# lmx2572_single_ended.net
KiCad netlist of a schematic drawn in EAGLE
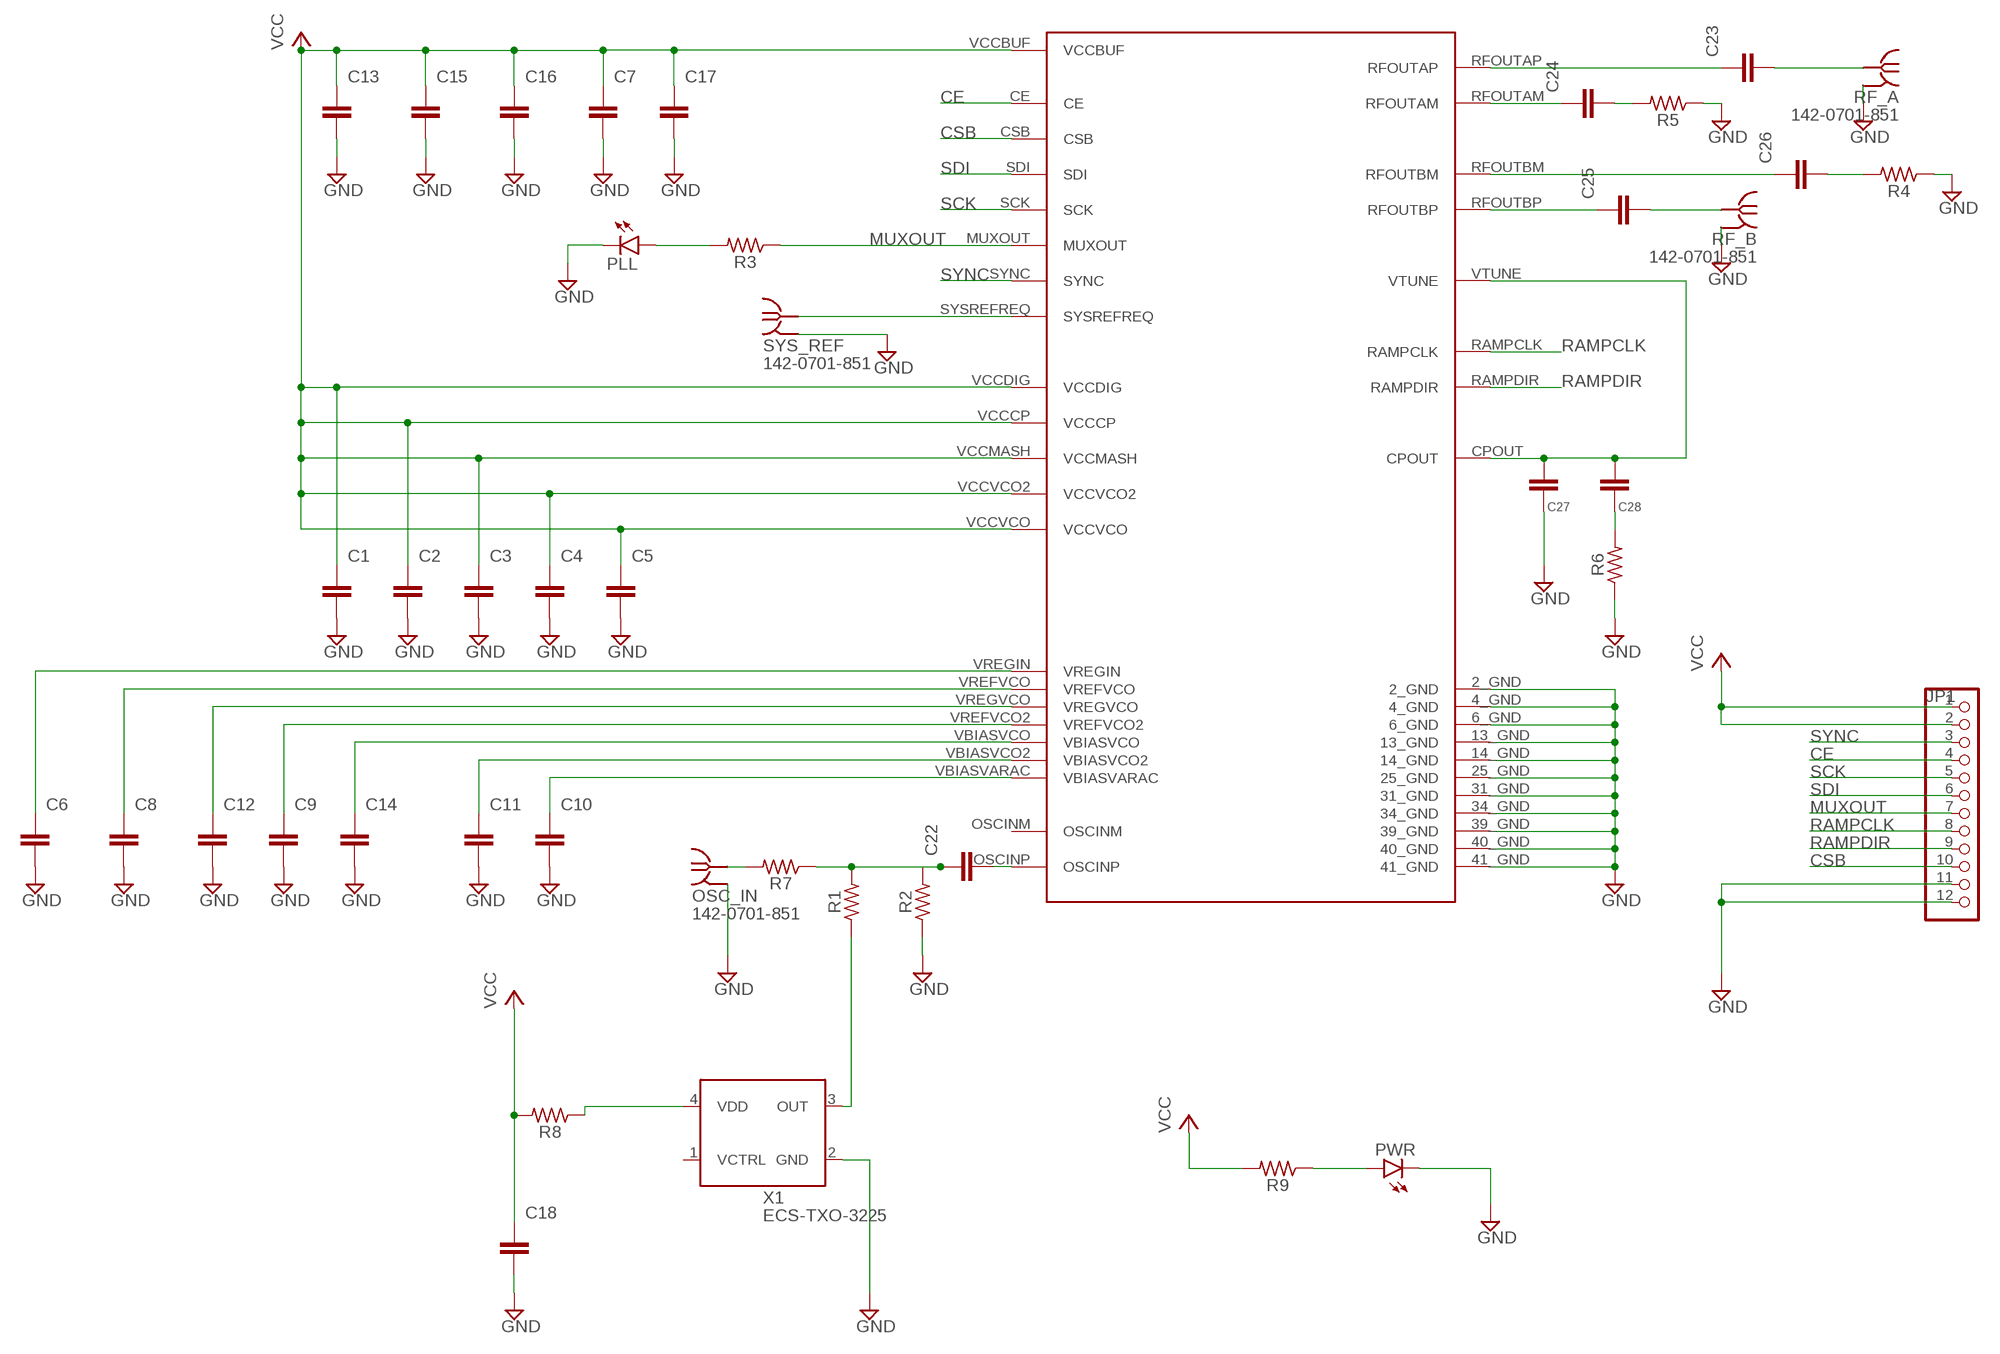
[diagram p0: schematic, sheet 1]

(export (version "E")
  (design (tool "Eeschema 10.0.6"))
  (components
    (comp (ref "C1")
      (value "1.0uF")
      (footprint "eagle-import:.0603-B-NOSILK")
      (libsource (lib "eagle-import") (part "C-EU0603-B-NOSILK"))
    )
    (comp (ref "C2")
      (value "1.0uF")
      (footprint "eagle-import:.0603-B-NOSILK")
      (libsource (lib "eagle-import") (part "C-EU0603-B-NOSILK"))
    )
    (comp (ref "C3")
      (value "1.0uF")
      (footprint "eagle-import:.0603-B-NOSILK")
      (libsource (lib "eagle-import") (part "C-EU0603-B-NOSILK"))
    )
    (comp (ref "C4")
      (value "1.0uF")
      (footprint "eagle-import:.0603-B-NOSILK")
      (libsource (lib "eagle-import") (part "C-EU0603-B-NOSILK"))
    )
    (comp (ref "C5")
      (value "1.0uF")
      (footprint "eagle-import:.0603-B-NOSILK")
      (libsource (lib "eagle-import") (part "C-EU0603-B-NOSILK"))
    )
    (comp (ref "C6")
      (value "1.0uF")
      (footprint "eagle-import:.0603-B-NOSILK")
      (libsource (lib "eagle-import") (part "C-EU0603-B-NOSILK"))
    )
    (comp (ref "C7")
      (value "0.1uF")
      (footprint "eagle-import:.0603-B-NOSILK")
      (libsource (lib "eagle-import") (part "C-EU0603-B-NOSILK"))
    )
    (comp (ref "C8")
      (value "10uF")
      (footprint "eagle-import:.0603-B-NOSILK")
      (libsource (lib "eagle-import") (part "C-EU0603-B-NOSILK"))
    )
    (comp (ref "C9")
      (value "10uF")
      (footprint "eagle-import:.0603-B-NOSILK")
      (libsource (lib "eagle-import") (part "C-EU0603-B-NOSILK"))
    )
    (comp (ref "C10")
      (value "10uF")
      (footprint "eagle-import:.0603-B-NOSILK")
      (libsource (lib "eagle-import") (part "C-EU0603-B-NOSILK"))
    )
    (comp (ref "C11")
      (value "0.1uF")
      (footprint "eagle-import:.0603-B-NOSILK")
      (libsource (lib "eagle-import") (part "C-EU0603-B-NOSILK"))
    )
    (comp (ref "C12")
      (value "10nF")
      (footprint "eagle-import:.0603-B-NOSILK")
      (libsource (lib "eagle-import") (part "C-EU0603-B-NOSILK"))
    )
    (comp (ref "C13")
      (value "0.1uF")
      (footprint "eagle-import:.0603-B-NOSILK")
      (libsource (lib "eagle-import") (part "C-EU0603-B-NOSILK"))
    )
    (comp (ref "C14")
      (value "470pF")
      (footprint "eagle-import:.0603-B-NOSILK")
      (libsource (lib "eagle-import") (part "C-EU0603-B-NOSILK"))
    )
    (comp (ref "C15")
      (value "10uF")
      (footprint "eagle-import:.0603-B-NOSILK")
      (libsource (lib "eagle-import") (part "C-EU0603-B-NOSILK"))
    )
    (comp (ref "C16")
      (value "10uF")
      (footprint "eagle-import:.0603-B-NOSILK")
      (libsource (lib "eagle-import") (part "C-EU0603-B-NOSILK"))
    )
    (comp (ref "C17")
      (value "0.1uF")
      (footprint "eagle-import:.0603-B-NOSILK")
      (libsource (lib "eagle-import") (part "C-EU0603-B-NOSILK"))
    )
    (comp (ref "C18")
      (value "10uF")
      (footprint "eagle-import:.0603-B-NOSILK")
      (libsource (lib "eagle-import") (part "C-EU0603-B-NOSILK"))
    )
    (comp (ref "C22")
      (value "0.1uF")
      (footprint "eagle-import:.0402-C-NOSILK")
      (libsource (lib "eagle-import") (part "C-EU0402-C-NOSILK"))
    )
    (comp (ref "C23")
      (value "100PF")
      (footprint "eagle-import:.0402-C-NOSILK")
      (libsource (lib "eagle-import") (part "C-EU0402-C-NOSILK"))
    )
    (comp (ref "C24")
      (value "100PF")
      (footprint "eagle-import:.0402-C-NOSILK")
      (libsource (lib "eagle-import") (part "C-EU0402-C-NOSILK"))
    )
    (comp (ref "C25")
      (value "100PF")
      (footprint "eagle-import:.0402-C-NOSILK")
      (libsource (lib "eagle-import") (part "C-EU0402-C-NOSILK"))
    )
    (comp (ref "C26")
      (value "100PF")
      (footprint "eagle-import:.0402-C-NOSILK")
      (libsource (lib "eagle-import") (part "C-EU0402-C-NOSILK"))
    )
    (comp (ref "C27")
      (value "4.7nf")
      (footprint "eagle-import:.0402-C-NOSILK")
      (libsource (lib "eagle-import") (part "C-EU0402-C-NOSILK"))
    )
    (comp (ref "C28")
      (value "220nf")
      (footprint "eagle-import:.0402-C-NOSILK")
      (libsource (lib "eagle-import") (part "C-EU0402-C-NOSILK"))
    )
    (comp (ref "JP1")
      (value "PINHD-1X12")
      (footprint "eagle-import:1X12")
      (libsource (lib "eagle-import") (part "PINHD-1X12"))
    )
    (comp (ref "OSC_IN")
      (value "142-0701-851")
      (footprint "eagle-import:142-0701-851")
      (libsource (lib "eagle-import") (part "142-0701-851"))
    )
    (comp (ref "PLL")
      (value "LEDCHIP-LED0603")
      (footprint "eagle-import:CHIP-LED0603")
      (libsource (lib "eagle-import") (part "LEDCHIP-LED0603"))
    )
    (comp (ref "PWR")
      (value "LEDCHIP-LED0603")
      (footprint "eagle-import:CHIP-LED0603")
      (libsource (lib "eagle-import") (part "LEDCHIP-LED0603"))
    )
    (comp (ref "R1")
      (value "0")
      (footprint "eagle-import:.0402-C-NOSILK")
      (libsource (lib "eagle-import") (part "R-US_0402-C-NOSILK"))
    )
    (comp (ref "R2")
      (value "50")
      (footprint "eagle-import:.0402-C-NOSILK")
      (libsource (lib "eagle-import") (part "R-US_0402-C-NOSILK"))
    )
    (comp (ref "R3")
      (value "330")
      (footprint "eagle-import:.0603-B-NOSILK")
      (libsource (lib "eagle-import") (part "R-US_0603-B-NOSILK"))
    )
    (comp (ref "R4")
      (value "50")
      (footprint "eagle-import:.0402-C-NOSILK")
      (libsource (lib "eagle-import") (part "R-US_0402-C-NOSILK"))
    )
    (comp (ref "R5")
      (value "50")
      (footprint "eagle-import:.0402-C-NOSILK")
      (libsource (lib "eagle-import") (part "R-US_0402-C-NOSILK"))
    )
    (comp (ref "R6")
      (value "100")
      (footprint "eagle-import:.0402-C-NOSILK")
      (libsource (lib "eagle-import") (part "R-US_0402-C-NOSILK"))
    )
    (comp (ref "R7")
      (value "0")
      (footprint "eagle-import:.0402-C-NOSILK")
      (libsource (lib "eagle-import") (part "R-US_0402-C-NOSILK"))
    )
    (comp (ref "R8")
      (value "0")
      (footprint "eagle-import:.0402-C-NOSILK")
      (libsource (lib "eagle-import") (part "R-US_0402-C-NOSILK"))
    )
    (comp (ref "R9")
      (value "330")
      (footprint "eagle-import:.0603-B-NOSILK")
      (libsource (lib "eagle-import") (part "R-US_0603-B-NOSILK"))
    )
    (comp (ref "RF_A")
      (value "142-0701-851")
      (footprint "eagle-import:142-0701-851")
      (libsource (lib "eagle-import") (part "142-0701-851"))
    )
    (comp (ref "RF_B")
      (value "142-0701-851")
      (footprint "eagle-import:142-0701-851")
      (libsource (lib "eagle-import") (part "142-0701-851"))
    )
    (comp (ref "SYS_REF")
      (value "142-0701-851")
      (footprint "eagle-import:142-0701-851")
      (libsource (lib "eagle-import") (part "142-0701-851"))
    )
    (comp (ref "U$1")
      (value "LMX2572_QFN")
      (footprint "eagle-import:LMX2572_QFN")
      (libsource (lib "eagle-import") (part "LMX2572_QFN"))
    )
    (comp (ref "X1")
      (value "ECS-TXO-3225")
      (footprint "eagle-import:3.2X2.5")
      (libsource (lib "eagle-import") (part "ECS-TXO-3225"))
    )
  )
  (nets
    (net (code "1") (name "/CE") (class "Default")
      (node (ref "JP1") (pin "4") (pinfunction "4_4") (pintype "passive"))
      (node (ref "U$1") (pin "CE") (pinfunction "CE_CE") (pintype "bidirectional"))
    )
    (net (code "2") (name "/CSB") (class "Default")
      (node (ref "JP1") (pin "10") (pinfunction "10_10") (pintype "passive"))
      (node (ref "U$1") (pin "CSB") (pinfunction "CSB_CSB") (pintype "bidirectional"))
    )
    (net (code "3") (name "/MUXOUT") (class "Default")
      (node (ref "JP1") (pin "7") (pinfunction "7_7") (pintype "passive"))
      (node (ref "R3") (pin "1") (pinfunction "1_1") (pintype "passive"))
      (node (ref "U$1") (pin "MUXOUT") (pinfunction "MUXOUT_MUXOUT") (pintype "bidirectional"))
    )
    (net (code "4") (name "/RAMPCLK") (class "Default")
      (node (ref "JP1") (pin "8") (pinfunction "8_8") (pintype "passive"))
      (node (ref "U$1") (pin "RAMPCLK") (pinfunction "RAMPCLK_RAMPCLK") (pintype "bidirectional"))
    )
    (net (code "5") (name "/RAMPDIR") (class "Default")
      (node (ref "JP1") (pin "9") (pinfunction "9_9") (pintype "passive"))
      (node (ref "U$1") (pin "RAMPDIR") (pinfunction "RAMPDIR_RAMPDIR") (pintype "bidirectional"))
    )
    (net (code "6") (name "/SCK") (class "Default")
      (node (ref "JP1") (pin "5") (pinfunction "5_5") (pintype "passive"))
      (node (ref "U$1") (pin "SCK") (pinfunction "SCK_SCK") (pintype "bidirectional"))
    )
    (net (code "7") (name "/SDI") (class "Default")
      (node (ref "JP1") (pin "6") (pinfunction "6_6") (pintype "passive"))
      (node (ref "U$1") (pin "SDI") (pinfunction "SDI_SDI") (pintype "bidirectional"))
    )
    (net (code "8") (name "/SYNC") (class "Default")
      (node (ref "JP1") (pin "3") (pinfunction "3_3") (pintype "passive"))
      (node (ref "U$1") (pin "SYNC") (pinfunction "SYNC_SYNC") (pintype "bidirectional"))
    )
    (net (code "9") (name "GND") (class "Default")
      (node (ref "C1") (pin "2") (pinfunction "2_2") (pintype "passive"))
      (node (ref "C10") (pin "2") (pinfunction "2_2") (pintype "passive"))
      (node (ref "C11") (pin "2") (pinfunction "2_2") (pintype "passive"))
      (node (ref "C12") (pin "2") (pinfunction "2_2") (pintype "passive"))
      (node (ref "C13") (pin "2") (pinfunction "2_2") (pintype "passive"))
      (node (ref "C14") (pin "2") (pinfunction "2_2") (pintype "passive"))
      (node (ref "C15") (pin "2") (pinfunction "2_2") (pintype "passive"))
      (node (ref "C16") (pin "2") (pinfunction "2_2") (pintype "passive"))
      (node (ref "C17") (pin "2") (pinfunction "2_2") (pintype "passive"))
      (node (ref "C18") (pin "2") (pinfunction "2_2") (pintype "passive"))
      (node (ref "C2") (pin "2") (pinfunction "2_2") (pintype "passive"))
      (node (ref "C27") (pin "1") (pinfunction "1_1") (pintype "passive"))
      (node (ref "C3") (pin "2") (pinfunction "2_2") (pintype "passive"))
      (node (ref "C4") (pin "2") (pinfunction "2_2") (pintype "passive"))
      (node (ref "C5") (pin "2") (pinfunction "2_2") (pintype "passive"))
      (node (ref "C6") (pin "2") (pinfunction "2_2") (pintype "passive"))
      (node (ref "C7") (pin "2") (pinfunction "2_2") (pintype "passive"))
      (node (ref "C8") (pin "2") (pinfunction "2_2") (pintype "passive"))
      (node (ref "C9") (pin "2") (pinfunction "2_2") (pintype "passive"))
      (node (ref "JP1") (pin "11") (pinfunction "11_11") (pintype "passive"))
      (node (ref "JP1") (pin "12") (pinfunction "12_12") (pintype "passive"))
      (node (ref "OSC_IN") (pin "GND1") (pinfunction "GND_GND1") (pintype "bidirectional"))
      (node (ref "OSC_IN") (pin "GND2") (pinfunction "GND_GND2") (pintype "bidirectional"))
      (node (ref "OSC_IN") (pin "GND3") (pinfunction "GND_GND3") (pintype "bidirectional"))
      (node (ref "OSC_IN") (pin "GND4") (pinfunction "GND_GND4") (pintype "bidirectional"))
      (node (ref "PLL") (pin "C") (pinfunction "C_C") (pintype "passive"))
      (node (ref "PWR") (pin "C") (pinfunction "C_C") (pintype "passive"))
      (node (ref "R2") (pin "1") (pinfunction "1_1") (pintype "passive"))
      (node (ref "R4") (pin "1") (pinfunction "1_1") (pintype "passive"))
      (node (ref "R5") (pin "1") (pinfunction "1_1") (pintype "passive"))
      (node (ref "R6") (pin "1") (pinfunction "1_1") (pintype "passive"))
      (node (ref "RF_A") (pin "GND1") (pinfunction "GND_GND1") (pintype "bidirectional"))
      (node (ref "RF_A") (pin "GND2") (pinfunction "GND_GND2") (pintype "bidirectional"))
      (node (ref "RF_A") (pin "GND3") (pinfunction "GND_GND3") (pintype "bidirectional"))
      (node (ref "RF_A") (pin "GND4") (pinfunction "GND_GND4") (pintype "bidirectional"))
      (node (ref "RF_B") (pin "GND1") (pinfunction "GND_GND1") (pintype "bidirectional"))
      (node (ref "RF_B") (pin "GND2") (pinfunction "GND_GND2") (pintype "bidirectional"))
      (node (ref "RF_B") (pin "GND3") (pinfunction "GND_GND3") (pintype "bidirectional"))
      (node (ref "RF_B") (pin "GND4") (pinfunction "GND_GND4") (pintype "bidirectional"))
      (node (ref "SYS_REF") (pin "GND1") (pinfunction "GND_GND1") (pintype "bidirectional"))
      (node (ref "SYS_REF") (pin "GND2") (pinfunction "GND_GND2") (pintype "bidirectional"))
      (node (ref "SYS_REF") (pin "GND3") (pinfunction "GND_GND3") (pintype "bidirectional"))
      (node (ref "SYS_REF") (pin "GND4") (pinfunction "GND_GND4") (pintype "bidirectional"))
      (node (ref "U$1") (pin "13_GND") (pinfunction "13_GND_13_GND") (pintype "bidirectional"))
      (node (ref "U$1") (pin "14_GND") (pinfunction "14_GND_14_GND") (pintype "bidirectional"))
      (node (ref "U$1") (pin "25_GND") (pinfunction "25_GND_25_GND") (pintype "bidirectional"))
      (node (ref "U$1") (pin "2_GND") (pinfunction "2_GND_2_GND") (pintype "bidirectional"))
      (node (ref "U$1") (pin "31_GND") (pinfunction "31_GND_31_GND") (pintype "bidirectional"))
      (node (ref "U$1") (pin "34_GND") (pinfunction "34_GND_34_GND") (pintype "bidirectional"))
      (node (ref "U$1") (pin "39_GND") (pinfunction "39_GND_39_GND") (pintype "bidirectional"))
      (node (ref "U$1") (pin "40_GND") (pinfunction "40_GND_40_GND") (pintype "bidirectional"))
      (node (ref "U$1") (pin "41_GND") (pinfunction "41_GND_41_GND") (pintype "bidirectional"))
      (node (ref "U$1") (pin "4_GND") (pinfunction "4_GND_4_GND") (pintype "bidirectional"))
      (node (ref "U$1") (pin "6_GND") (pinfunction "6_GND_6_GND") (pintype "bidirectional"))
      (node (ref "X1") (pin "2") (pinfunction "GND_2") (pintype "power_in"))
    )
    (net (code "10") (name "Net-(C6-Pad1)") (class "Default")
      (node (ref "C6") (pin "1") (pinfunction "1_1") (pintype "passive"))
      (node (ref "U$1") (pin "VREGIN") (pinfunction "VREGIN_VREGIN") (pintype "bidirectional"))
    )
    (net (code "11") (name "Net-(C8-Pad1)") (class "Default")
      (node (ref "C8") (pin "1") (pinfunction "1_1") (pintype "passive"))
      (node (ref "U$1") (pin "VREFVCO") (pinfunction "VREFVCO_VREFVCO") (pintype "bidirectional"))
    )
    (net (code "12") (name "Net-(C9-Pad1)") (class "Default")
      (node (ref "C9") (pin "1") (pinfunction "1_1") (pintype "passive"))
      (node (ref "U$1") (pin "VREFVCO2") (pinfunction "VREFVCO2_VREFVCO2") (pintype "bidirectional"))
    )
    (net (code "13") (name "Net-(C10-Pad1)") (class "Default")
      (node (ref "C10") (pin "1") (pinfunction "1_1") (pintype "passive"))
      (node (ref "U$1") (pin "VBIASVARAC") (pinfunction "VBIASVARAC_VBIASVARAC") (pintype "bidirectional"))
    )
    (net (code "14") (name "Net-(C11-Pad1)") (class "Default")
      (node (ref "C11") (pin "1") (pinfunction "1_1") (pintype "passive"))
      (node (ref "U$1") (pin "VBIASVCO2") (pinfunction "VBIASVCO2_VBIASVCO2") (pintype "bidirectional"))
    )
    (net (code "15") (name "Net-(C12-Pad1)") (class "Default")
      (node (ref "C12") (pin "1") (pinfunction "1_1") (pintype "passive"))
      (node (ref "U$1") (pin "VREGVCO") (pinfunction "VREGVCO_VREGVCO") (pintype "bidirectional"))
    )
    (net (code "16") (name "Net-(C14-Pad1)") (class "Default")
      (node (ref "C14") (pin "1") (pinfunction "1_1") (pintype "passive"))
      (node (ref "U$1") (pin "VBIASVCO") (pinfunction "VBIASVCO_VBIASVCO") (pintype "bidirectional"))
    )
    (net (code "17") (name "Net-(C22-Pad1)") (class "Default")
      (node (ref "C22") (pin "1") (pinfunction "1_1") (pintype "passive"))
      (node (ref "R1") (pin "2") (pinfunction "2_2") (pintype "passive"))
      (node (ref "R2") (pin "2") (pinfunction "2_2") (pintype "passive"))
      (node (ref "R7") (pin "1") (pinfunction "1_1") (pintype "passive"))
    )
    (net (code "18") (name "Net-(C22-Pad2)") (class "Default")
      (node (ref "C22") (pin "2") (pinfunction "2_2") (pintype "passive"))
      (node (ref "U$1") (pin "OSCINP") (pinfunction "OSCINP_OSCINP") (pintype "bidirectional"))
    )
    (net (code "19") (name "Net-(C23-Pad1)") (class "Default")
      (node (ref "C23") (pin "1") (pinfunction "1_1") (pintype "passive"))
      (node (ref "U$1") (pin "RFOUTAP") (pinfunction "RFOUTAP_RFOUTAP") (pintype "bidirectional"))
    )
    (net (code "20") (name "Net-(C24-Pad1)") (class "Default")
      (node (ref "C24") (pin "1") (pinfunction "1_1") (pintype "passive"))
      (node (ref "U$1") (pin "RFOUTAM") (pinfunction "RFOUTAM_RFOUTAM") (pintype "bidirectional"))
    )
    (net (code "21") (name "Net-(C24-Pad2)") (class "Default")
      (node (ref "C24") (pin "2") (pinfunction "2_2") (pintype "passive"))
      (node (ref "R5") (pin "2") (pinfunction "2_2") (pintype "passive"))
    )
    (net (code "22") (name "Net-(C25-Pad1)") (class "Default")
      (node (ref "C25") (pin "1") (pinfunction "1_1") (pintype "passive"))
      (node (ref "U$1") (pin "RFOUTBP") (pinfunction "RFOUTBP_RFOUTBP") (pintype "bidirectional"))
    )
    (net (code "23") (name "Net-(C26-Pad1)") (class "Default")
      (node (ref "C26") (pin "1") (pinfunction "1_1") (pintype "passive"))
      (node (ref "U$1") (pin "RFOUTBM") (pinfunction "RFOUTBM_RFOUTBM") (pintype "bidirectional"))
    )
    (net (code "24") (name "Net-(C26-Pad2)") (class "Default")
      (node (ref "C26") (pin "2") (pinfunction "2_2") (pintype "passive"))
      (node (ref "R4") (pin "2") (pinfunction "2_2") (pintype "passive"))
    )
    (net (code "25") (name "Net-(C27-Pad2)") (class "Default")
      (node (ref "C27") (pin "2") (pinfunction "2_2") (pintype "passive"))
      (node (ref "C28") (pin "2") (pinfunction "2_2") (pintype "passive"))
      (node (ref "U$1") (pin "CPOUT") (pinfunction "CPOUT_CPOUT") (pintype "bidirectional"))
      (node (ref "U$1") (pin "VTUNE") (pinfunction "VTUNE_VTUNE") (pintype "bidirectional"))
    )
    (net (code "26") (name "Net-(C28-Pad1)") (class "Default")
      (node (ref "C28") (pin "1") (pinfunction "1_1") (pintype "passive"))
      (node (ref "R6") (pin "2") (pinfunction "2_2") (pintype "passive"))
    )
    (net (code "27") (name "Net-(OSC_IN-RF)") (class "Default")
      (node (ref "OSC_IN") (pin "RF1") (pinfunction "RF_RF1") (pintype "bidirectional"))
      (node (ref "R7") (pin "2") (pinfunction "2_2") (pintype "passive"))
    )
    (net (code "28") (name "Net-(PLL-PadA)") (class "Default")
      (node (ref "PLL") (pin "A") (pinfunction "A_A") (pintype "passive"))
      (node (ref "R3") (pin "2") (pinfunction "2_2") (pintype "passive"))
    )
    (net (code "29") (name "Net-(PWR-PadA)") (class "Default")
      (node (ref "PWR") (pin "A") (pinfunction "A_A") (pintype "passive"))
      (node (ref "R9") (pin "1") (pinfunction "1_1") (pintype "passive"))
    )
    (net (code "30") (name "Net-(RF_A-RF)") (class "Default")
      (node (ref "C23") (pin "2") (pinfunction "2_2") (pintype "passive"))
      (node (ref "RF_A") (pin "RF1") (pinfunction "RF_RF1") (pintype "bidirectional"))
    )
    (net (code "31") (name "Net-(RF_B-RF)") (class "Default")
      (node (ref "C25") (pin "2") (pinfunction "2_2") (pintype "passive"))
      (node (ref "RF_B") (pin "RF1") (pinfunction "RF_RF1") (pintype "bidirectional"))
    )
    (net (code "32") (name "Net-(SYS_REF-RF)") (class "Default")
      (node (ref "SYS_REF") (pin "RF1") (pinfunction "RF_RF1") (pintype "bidirectional"))
      (node (ref "U$1") (pin "SYSREFREQ") (pinfunction "SYSREFREQ_SYSREFREQ") (pintype "bidirectional"))
    )
    (net (code "33") (name "Net-(X1-OUT)") (class "Default")
      (node (ref "R1") (pin "1") (pinfunction "1_1") (pintype "passive"))
      (node (ref "X1") (pin "3") (pinfunction "OUT_3") (pintype "output"))
    )
    (net (code "34") (name "Net-(X1-VDD)") (class "Default")
      (node (ref "R8") (pin "1") (pinfunction "1_1") (pintype "passive"))
      (node (ref "X1") (pin "4") (pinfunction "VDD_4") (pintype "power_in"))
    )
    (net (code "35") (name "VCC") (class "Default")
      (node (ref "C1") (pin "1") (pinfunction "1_1") (pintype "passive"))
      (node (ref "C13") (pin "1") (pinfunction "1_1") (pintype "passive"))
      (node (ref "C15") (pin "1") (pinfunction "1_1") (pintype "passive"))
      (node (ref "C16") (pin "1") (pinfunction "1_1") (pintype "passive"))
      (node (ref "C17") (pin "1") (pinfunction "1_1") (pintype "passive"))
      (node (ref "C18") (pin "1") (pinfunction "1_1") (pintype "passive"))
      (node (ref "C2") (pin "1") (pinfunction "1_1") (pintype "passive"))
      (node (ref "C3") (pin "1") (pinfunction "1_1") (pintype "passive"))
      (node (ref "C4") (pin "1") (pinfunction "1_1") (pintype "passive"))
      (node (ref "C5") (pin "1") (pinfunction "1_1") (pintype "passive"))
      (node (ref "C7") (pin "1") (pinfunction "1_1") (pintype "passive"))
      (node (ref "JP1") (pin "1") (pinfunction "1_1") (pintype "passive"))
      (node (ref "JP1") (pin "2") (pinfunction "2_2") (pintype "passive"))
      (node (ref "R8") (pin "2") (pinfunction "2_2") (pintype "passive"))
      (node (ref "R9") (pin "2") (pinfunction "2_2") (pintype "passive"))
      (node (ref "U$1") (pin "VCCBUF") (pinfunction "VCCBUF_VCCBUF") (pintype "bidirectional"))
      (node (ref "U$1") (pin "VCCCP") (pinfunction "VCCCP_VCCCP") (pintype "bidirectional"))
      (node (ref "U$1") (pin "VCCDIG") (pinfunction "VCCDIG_VCCDIG") (pintype "bidirectional"))
      (node (ref "U$1") (pin "VCCMASH") (pinfunction "VCCMASH_VCCMASH") (pintype "bidirectional"))
      (node (ref "U$1") (pin "VCCVCO") (pinfunction "VCCVCO_VCCVCO") (pintype "bidirectional"))
      (node (ref "U$1") (pin "VCCVCO2") (pinfunction "VCCVCO2_VCCVCO2") (pintype "bidirectional"))
    )
    (net (code "36") (name "unconnected-(U$1-PadOSCINM)") (class "Default")
      (node (ref "U$1") (pin "OSCINM") (pinfunction "OSCINM_OSCINM") (pintype "bidirectional"))
    )
    (net (code "37") (name "unconnected-(X1-VCTRL-Pad1)") (class "Default")
      (node (ref "X1") (pin "1") (pinfunction "VCTRL_1") (pintype "input"))
    )
  )
)
